# STM32_microcontroller_Power.net
KiCad netlist of a schematic drawn in Altium Designer
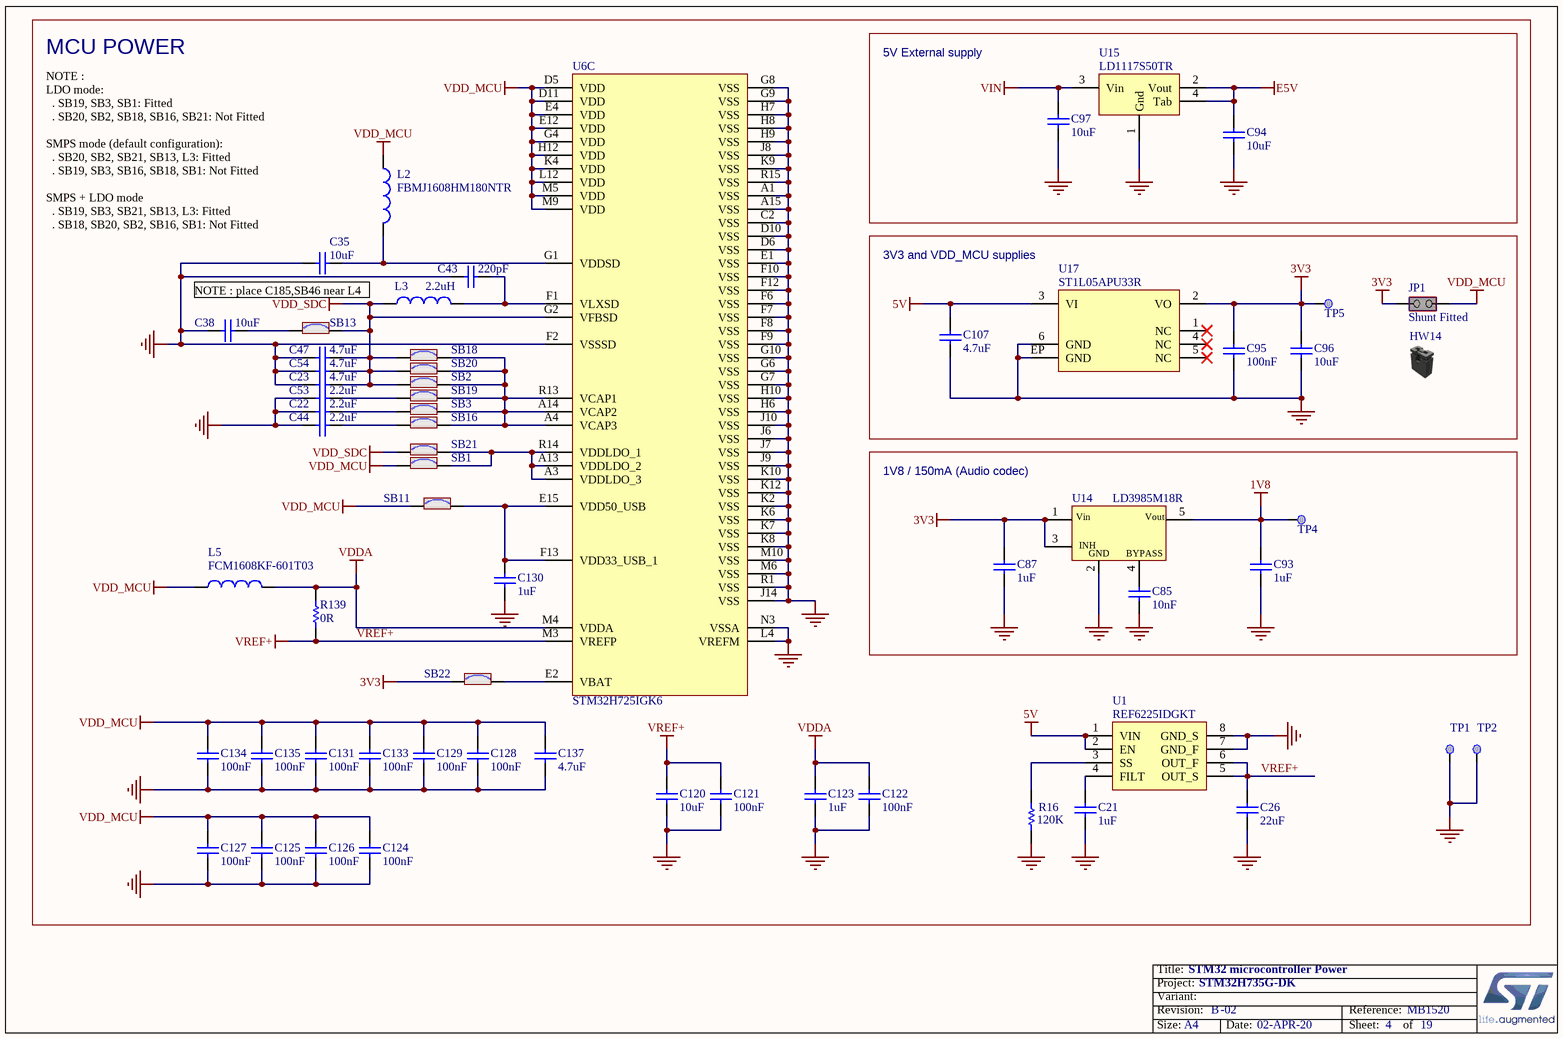
[diagram p0: STM32 microcontroller Power.SchDoc]

(export (version "E")
  (design (tool "Eeschema 10.0.6"))
  (components
    (comp (ref "C21")
      (value "1uF")
      (footprint "C0603")
      (description "Capacitor, MLCC, 1uF, 16V, X5R, 10%, 0603, T=0,8mm")
      (fields
        (field (name "INTERNAL_PART_NUMBER") "MCD-00010")
        (field (name "MANUFACTURER_PART_NUMBER") "CC0603KRX5R7BB105")
        (field (name "PROVIDED_BY") "SUBCO")
      )
      (libsource (lib "MCD_PARTS_database") (part "Capacitor"))
    )
    (comp (ref "C22")
      (value "2.2uF")
      (footprint "C0603")
      (description "Capacitor, MLCC, 2.2uF, 10V, X5R, 10%, 0603, T=0,8mm")
      (fields
        (field (name "INTERNAL_PART_NUMBER") "MCD-00012")
        (field (name "MANUFACTURER_PART_NUMBER") "CC0603KRX5R6BB225")
        (field (name "PROVIDED_BY") "SUBCO")
      )
      (libsource (lib "MCD_PARTS_database") (part "Capacitor"))
    )
    (comp (ref "C23")
      (value "4.7uF")
      (footprint "C0402")
      (description "Capacitor, MLCC, 4.7uF, 6V3, X5R, 20%, 0402, T=0,5mm")
      (fields
        (field (name "INTERNAL_PART_NUMBER") "MCD-01356")
        (field (name "MANUFACTURER_PART_NUMBER") "GRM155R60J475ME47")
        (field (name "PROVIDED_BY") "SUBCO")
      )
      (libsource (lib "MCD_PARTS_database") (part "Capacitor"))
    )
    (comp (ref "C26")
      (value "22uF")
      (footprint "C1210")
      (description "Capacitor, MLCC, 22uF, 16V, 1210, X7R, 20%, T=2,5mm, ESR 2mohm@410KHz")
      (fields
        (field (name "INTERNAL_PART_NUMBER") "MCD-00614")
        (field (name "MANUFACTURER_PART_NUMBER") "GCM32ER71C226ME19")
        (field (name "PROVIDED_BY") "SUBCO")
      )
      (libsource (lib "MCD_PARTS_database") (part "Capacitor"))
    )
    (comp (ref "C35")
      (value "10uF")
      (footprint "C0402")
      (description "Capacitor, MLCC, 10uF, 4V, X5R, 20%, 0402, T=0,5mm")
      (fields
        (field (name "INTERNAL_PART_NUMBER") "MCD-01355")
        (field (name "MANUFACTURER_PART_NUMBER") "GRM155R60G106ME44")
        (field (name "PROVIDED_BY") "SUBCO")
      )
      (libsource (lib "MCD_PARTS_database") (part "Capacitor"))
    )
    (comp (ref "C38")
      (value "10uF")
      (footprint "C0603")
      (description "Capacitor, MLCC, 10uF, 6V3, X5R, 20%, 0603, T=0,8mm")
      (fields
        (field (name "INTERNAL_PART_NUMBER") "MCD-01341")
        (field (name "MANUFACTURER_PART_NUMBER") "GRM188R60J106ME47D")
        (field (name "PROVIDED_BY") "SUBCO")
      )
      (libsource (lib "MCD_PARTS_database") (part "Capacitor"))
    )
    (comp (ref "C43")
      (value "220pF")
      (footprint "C0402")
      (description "Capacitor, MLCC, 220pF, 50V, NPO, 5%, 0402, T=0,5mm")
      (fields
        (field (name "INTERNAL_PART_NUMBER") "MCD-01225")
        (field (name "MANUFACTURER_PART_NUMBER") "CC0402JRNPO9BN221")
        (field (name "PROVIDED_BY") "SUBCO")
      )
      (libsource (lib "MCD_PARTS_database") (part "Capacitor"))
    )
    (comp (ref "C44")
      (value "2.2uF")
      (footprint "C0603")
      (description "Capacitor, MLCC, 2.2uF, 10V, X5R, 10%, 0603, T=0,8mm")
      (fields
        (field (name "INTERNAL_PART_NUMBER") "MCD-00012")
        (field (name "MANUFACTURER_PART_NUMBER") "CC0603KRX5R6BB225")
        (field (name "PROVIDED_BY") "SUBCO")
      )
      (libsource (lib "MCD_PARTS_database") (part "Capacitor"))
    )
    (comp (ref "C47")
      (value "4.7uF")
      (footprint "C0402")
      (description "Capacitor, MLCC, 4.7uF, 6V3, X5R, 20%, 0402, T=0,5mm")
      (fields
        (field (name "INTERNAL_PART_NUMBER") "MCD-01356")
        (field (name "MANUFACTURER_PART_NUMBER") "GRM155R60J475ME47")
        (field (name "PROVIDED_BY") "SUBCO")
      )
      (libsource (lib "MCD_PARTS_database") (part "Capacitor"))
    )
    (comp (ref "C53")
      (value "2.2uF")
      (footprint "C0603")
      (description "Capacitor, MLCC, 2.2uF, 10V, X5R, 10%, 0603, T=0,8mm")
      (fields
        (field (name "INTERNAL_PART_NUMBER") "MCD-00012")
        (field (name "MANUFACTURER_PART_NUMBER") "CC0603KRX5R6BB225")
        (field (name "PROVIDED_BY") "SUBCO")
      )
      (libsource (lib "MCD_PARTS_database") (part "Capacitor"))
    )
    (comp (ref "C54")
      (value "4.7uF")
      (footprint "C0402")
      (description "Capacitor, MLCC, 4.7uF, 6V3, X5R, 20%, 0402, T=0,5mm")
      (fields
        (field (name "INTERNAL_PART_NUMBER") "MCD-01356")
        (field (name "MANUFACTURER_PART_NUMBER") "GRM155R60J475ME47")
        (field (name "PROVIDED_BY") "SUBCO")
      )
      (libsource (lib "MCD_PARTS_database") (part "Capacitor"))
    )
    (comp (ref "C85")
      (value "10nF")
      (footprint "C0402")
      (description "Capacitor, MLCC, 10nF, 16V, X7R, 10%, 0402, T=0.5mm")
      (fields
        (field (name "INTERNAL_PART_NUMBER") "MCD-00011")
        (field (name "MANUFACTURER_PART_NUMBER") "CC0402KRX7R7BB103")
        (field (name "PROVIDED_BY") "SUBCO")
      )
      (libsource (lib "MCD_PARTS_database") (part "Capacitor"))
    )
    (comp (ref "C87")
      (value "1uF")
      (footprint "C0402")
      (description "Capacitor, MLCC, 1uF, 6V3, X5R, 10%, 0402, T=0,5mm")
      (fields
        (field (name "INTERNAL_PART_NUMBER") "MCD-00095")
        (field (name "MANUFACTURER_PART_NUMBER") "GRM155R61E105KA12")
        (field (name "PROVIDED_BY") "SUBCO")
      )
      (libsource (lib "MCD_PARTS_database") (part "Capacitor"))
    )
    (comp (ref "C93")
      (value "1uF")
      (footprint "C0402")
      (description "Capacitor, MLCC, 1uF, 6V3, X5R, 10%, 0402, T=0,5mm")
      (fields
        (field (name "INTERNAL_PART_NUMBER") "MCD-00095")
        (field (name "MANUFACTURER_PART_NUMBER") "GRM155R61E105KA12")
        (field (name "PROVIDED_BY") "SUBCO")
      )
      (libsource (lib "MCD_PARTS_database") (part "Capacitor"))
    )
    (comp (ref "C94")
      (value "10uF")
      (footprint "C0805")
      (description "Capacitor, MLCC, 10uF, 25V, X5R, 10%, 0805, T=0,85mm")
      (fields
        (field (name "INTERNAL_PART_NUMBER") "MCD-00014")
        (field (name "MANUFACTURER_PART_NUMBER") "CC0805KRX5R8BB106")
        (field (name "PROVIDED_BY") "SUBCO")
      )
      (libsource (lib "MCD_PARTS_database") (part "Capacitor"))
    )
    (comp (ref "C95")
      (value "100nF")
      (footprint "C0402")
      (description "Capacitor, MLCC, 100nF, 16V, X7R, 10%, 0402, T=0,5mm")
      (fields
        (field (name "INTERNAL_PART_NUMBER") "MCD-00102")
        (field (name "MANUFACTURER_PART_NUMBER") "CC0402KRX7R7BB104")
        (field (name "PROVIDED_BY") "SUBCO")
      )
      (libsource (lib "MCD_PARTS_database") (part "Capacitor"))
    )
    (comp (ref "C96")
      (value "10uF")
      (footprint "C0805")
      (description "Capacitor, MLCC, 10uF, 25V, X5R, 10%, 0805, T=0,85mm")
      (fields
        (field (name "INTERNAL_PART_NUMBER") "MCD-00014")
        (field (name "MANUFACTURER_PART_NUMBER") "CC0805KRX5R8BB106")
        (field (name "PROVIDED_BY") "SUBCO")
      )
      (libsource (lib "MCD_PARTS_database") (part "Capacitor"))
    )
    (comp (ref "C97")
      (value "10uF")
      (footprint "C0805")
      (description "Capacitor, MLCC, 10uF, 25V, X5R, 10%, 0805, T=0,85mm")
      (fields
        (field (name "INTERNAL_PART_NUMBER") "MCD-00014")
        (field (name "MANUFACTURER_PART_NUMBER") "CC0805KRX5R8BB106")
        (field (name "PROVIDED_BY") "SUBCO")
      )
      (libsource (lib "MCD_PARTS_database") (part "Capacitor"))
    )
    (comp (ref "C107")
      (value "4.7uF")
      (footprint "C0603")
      (description "Capacitor, MLCC, 4.7uF, 16V, X5R, 20%, 0603, T=0,8mm")
      (fields
        (field (name "INTERNAL_PART_NUMBER") "MCD-00097")
        (field (name "MANUFACTURER_PART_NUMBER") "GRM188R61C475KE11")
        (field (name "PROVIDED_BY") "SUBCO")
      )
      (libsource (lib "MCD_PARTS_database") (part "Capacitor"))
    )
    (comp (ref "C120")
      (value "10uF")
      (footprint "C0805")
      (description "Capacitor, MLCC, 10uF, 25V, X5R, 10%, 0805, T=0,85mm")
      (fields
        (field (name "INTERNAL_PART_NUMBER") "MCD-00014")
        (field (name "MANUFACTURER_PART_NUMBER") "CC0805KRX5R8BB106")
        (field (name "PROVIDED_BY") "SUBCO")
      )
      (libsource (lib "MCD_PARTS_database") (part "Capacitor"))
    )
    (comp (ref "C121")
      (value "100nF")
      (footprint "C0402")
      (description "Capacitor, MLCC, 100nF, 16V, X7R, 10%, 0402, T=0,5mm")
      (fields
        (field (name "INTERNAL_PART_NUMBER") "MCD-00102")
        (field (name "MANUFACTURER_PART_NUMBER") "CC0402KRX7R7BB104")
        (field (name "PROVIDED_BY") "SUBCO")
      )
      (libsource (lib "MCD_PARTS_database") (part "Capacitor"))
    )
    (comp (ref "C122")
      (value "100nF")
      (footprint "C0402")
      (description "Capacitor, MLCC, 100nF, 16V, X7R, 10%, 0402, T=0,5mm")
      (fields
        (field (name "INTERNAL_PART_NUMBER") "MCD-00102")
        (field (name "MANUFACTURER_PART_NUMBER") "CC0402KRX7R7BB104")
        (field (name "PROVIDED_BY") "SUBCO")
      )
      (libsource (lib "MCD_PARTS_database") (part "Capacitor"))
    )
    (comp (ref "C123")
      (value "1uF")
      (footprint "C0402")
      (description "Capacitor, 1uF, 10V, X5R, 10%, 0402, T=0.5mm")
      (fields
        (field (name "INTERNAL_PART_NUMBER") "MCD-01722")
        (field (name "MANUFACTURER_PART_NUMBER") "CC0402KRX5R6BB105")
        (field (name "PROVIDED_BY") "SUBCO")
      )
      (libsource (lib "MCD_PARTS_database") (part "Capacitor"))
    )
    (comp (ref "C124")
      (value "100nF")
      (footprint "C0402")
      (description "Capacitor, MLCC, 100nF, 16V, X7R, 10%, 0402, T=0,5mm")
      (fields
        (field (name "INTERNAL_PART_NUMBER") "MCD-00102")
        (field (name "MANUFACTURER_PART_NUMBER") "CC0402KRX7R7BB104")
        (field (name "PROVIDED_BY") "SUBCO")
      )
      (libsource (lib "MCD_PARTS_database") (part "Capacitor"))
    )
    (comp (ref "C125")
      (value "100nF")
      (footprint "C0402")
      (description "Capacitor, MLCC, 100nF, 16V, X7R, 10%, 0402, T=0,5mm")
      (fields
        (field (name "INTERNAL_PART_NUMBER") "MCD-00102")
        (field (name "MANUFACTURER_PART_NUMBER") "CC0402KRX7R7BB104")
        (field (name "PROVIDED_BY") "SUBCO")
      )
      (libsource (lib "MCD_PARTS_database") (part "Capacitor"))
    )
    (comp (ref "C126")
      (value "100nF")
      (footprint "C0402")
      (description "Capacitor, MLCC, 100nF, 16V, X7R, 10%, 0402, T=0,5mm")
      (fields
        (field (name "INTERNAL_PART_NUMBER") "MCD-00102")
        (field (name "MANUFACTURER_PART_NUMBER") "CC0402KRX7R7BB104")
        (field (name "PROVIDED_BY") "SUBCO")
      )
      (libsource (lib "MCD_PARTS_database") (part "Capacitor"))
    )
    (comp (ref "C127")
      (value "100nF")
      (footprint "C0402")
      (description "Capacitor, MLCC, 100nF, 16V, X7R, 10%, 0402, T=0,5mm")
      (fields
        (field (name "INTERNAL_PART_NUMBER") "MCD-00102")
        (field (name "MANUFACTURER_PART_NUMBER") "CC0402KRX7R7BB104")
        (field (name "PROVIDED_BY") "SUBCO")
      )
      (libsource (lib "MCD_PARTS_database") (part "Capacitor"))
    )
    (comp (ref "C128")
      (value "100nF")
      (footprint "C0402")
      (description "Capacitor, MLCC, 100nF, 16V, X7R, 10%, 0402, T=0,5mm")
      (fields
        (field (name "INTERNAL_PART_NUMBER") "MCD-00102")
        (field (name "MANUFACTURER_PART_NUMBER") "CC0402KRX7R7BB104")
        (field (name "PROVIDED_BY") "SUBCO")
      )
      (libsource (lib "MCD_PARTS_database") (part "Capacitor"))
    )
    (comp (ref "C129")
      (value "100nF")
      (footprint "C0402")
      (description "Capacitor, MLCC, 100nF, 16V, X7R, 10%, 0402, T=0,5mm")
      (fields
        (field (name "INTERNAL_PART_NUMBER") "MCD-00102")
        (field (name "MANUFACTURER_PART_NUMBER") "CC0402KRX7R7BB104")
        (field (name "PROVIDED_BY") "SUBCO")
      )
      (libsource (lib "MCD_PARTS_database") (part "Capacitor"))
    )
    (comp (ref "C130")
      (value "1uF")
      (footprint "C0603")
      (description "Capacitor, MLCC, 1uF, 16V, X5R, 10%, 0603, T=0,8mm")
      (fields
        (field (name "INTERNAL_PART_NUMBER") "MCD-00010")
        (field (name "MANUFACTURER_PART_NUMBER") "CC0603KRX5R7BB105")
        (field (name "PROVIDED_BY") "SUBCO")
      )
      (libsource (lib "MCD_PARTS_database") (part "Capacitor"))
    )
    (comp (ref "C131")
      (value "100nF")
      (footprint "C0402")
      (description "Capacitor, MLCC, 100nF, 16V, X7R, 10%, 0402, T=0,5mm")
      (fields
        (field (name "INTERNAL_PART_NUMBER") "MCD-00102")
        (field (name "MANUFACTURER_PART_NUMBER") "CC0402KRX7R7BB104")
        (field (name "PROVIDED_BY") "SUBCO")
      )
      (libsource (lib "MCD_PARTS_database") (part "Capacitor"))
    )
    (comp (ref "C133")
      (value "100nF")
      (footprint "C0402")
      (description "Capacitor, MLCC, 100nF, 16V, X7R, 10%, 0402, T=0,5mm")
      (fields
        (field (name "INTERNAL_PART_NUMBER") "MCD-00102")
        (field (name "MANUFACTURER_PART_NUMBER") "CC0402KRX7R7BB104")
        (field (name "PROVIDED_BY") "SUBCO")
      )
      (libsource (lib "MCD_PARTS_database") (part "Capacitor"))
    )
    (comp (ref "C134")
      (value "100nF")
      (footprint "C0402")
      (description "Capacitor, MLCC, 100nF, 16V, X7R, 10%, 0402, T=0,5mm")
      (fields
        (field (name "INTERNAL_PART_NUMBER") "MCD-00102")
        (field (name "MANUFACTURER_PART_NUMBER") "CC0402KRX7R7BB104")
        (field (name "PROVIDED_BY") "SUBCO")
      )
      (libsource (lib "MCD_PARTS_database") (part "Capacitor"))
    )
    (comp (ref "C135")
      (value "100nF")
      (footprint "C0402")
      (description "Capacitor, MLCC, 100nF, 16V, X7R, 10%, 0402, T=0,5mm")
      (fields
        (field (name "INTERNAL_PART_NUMBER") "MCD-00102")
        (field (name "MANUFACTURER_PART_NUMBER") "CC0402KRX7R7BB104")
        (field (name "PROVIDED_BY") "SUBCO")
      )
      (libsource (lib "MCD_PARTS_database") (part "Capacitor"))
    )
    (comp (ref "C137")
      (value "4.7uF")
      (footprint "C0402")
      (description "Capacitor, MLCC, 4.7uF, 6V3, X5R, 20%, 0402, T=0,5mm")
      (fields
        (field (name "INTERNAL_PART_NUMBER") "MCD-01356")
        (field (name "MANUFACTURER_PART_NUMBER") "GRM155R60J475ME47")
        (field (name "PROVIDED_BY") "SUBCO")
      )
      (libsource (lib "MCD_PARTS_database") (part "Capacitor"))
    )
    (comp (ref "HW14")
      (value "Shunt Black 2.54mm")
      (description "SHUNT 2.54mm BLACK")
      (fields
        (field (name "INTERNAL_PART_NUMBER") "MCD-00043")
        (field (name "MANUFACTURER_PART_NUMBER") "SNT-100-BK-G")
        (field (name "PROVIDED_BY") "SUBCO")
      )
      (libsource (lib "MCD_PARTS_database") (part "Shunt Black 2.54mm"))
    )
    (comp (ref "JP1")
      (value "Shunt Fitted")
      (footprint "CON_SAMTEC_TSW-102-07-G-S")
      (description "Header, 2x1, 2,54mm, VR, TH, Height 5.84mm/2.54mm - Shunt Fitted by default")
      (fields
        (field (name "INTERNAL_PART_NUMBER") "MCD-00683")
        (field (name "MANUFACTURER_PART_NUMBER") "TSW-102-07-x-S")
        (field (name "PROVIDED_BY") "SUBCO")
      )
      (libsource (lib "MCD_PARTS_database") (part "Jumper_Header 2x1 Fitted"))
    )
    (comp (ref "L2")
      (value "FBMJ1608HM180NTR")
      (footprint "IND_TAIYO-YUDEN_FBMJ1608")
      (description "Ferrite Bead 18 ohm@100MHz 0603")
      (fields
        (field (name "INTERNAL_PART_NUMBER") "MCD-01431")
        (field (name "MANUFACTURER") "TAIYO YUDEN")
        (field (name "PROVIDED_BY") "SUBCO")
      )
      (libsource (lib "MCD_PARTS_database") (part "Inductor"))
    )
    (comp (ref "L3")
      (value "2.2uH")
      (footprint "IND_2016_MURATA_LQM2MPN2R2NG0")
      (description "Inductor 2.2uH, 2x1.6x0.9mm")
      (fields
        (field (name "INTERNAL_PART_NUMBER") "MCD-01110")
        (field (name "MANUFACTURER_PART_NUMBER") "LQM2MPN2R2NG0")
        (field (name "PROVIDED_BY") "SUBCO")
      )
      (libsource (lib "MCD_PARTS_database") (part "Inductor"))
    )
    (comp (ref "L5")
      (value "BEAD")
      (footprint "L0603")
      (description "SMD Chip ferrite bead, 600R@100MHz +/-25%, 350mA, 500mohm DC, 0603, T=0.8mm")
      (fields
        (field (name "INTERNAL_PART_NUMBER") "MCD-00047")
        (field (name "MANUFACTURER_PART_NUMBER") "FCM1608KF-601T03")
        (field (name "MANUFACTURER") "TAI-TECH")
        (field (name "PROVIDED_BY") "SUBCO")
      )
      (libsource (lib "MCD_PARTS_database") (part "BEAD"))
    )
    (comp (ref "R16")
      (value "120K")
      (footprint "R0402")
      (description "Resistor,120K,0402,1%,1/16W")
      (fields
        (field (name "INTERNAL_PART_NUMBER") "MCD-00166")
        (field (name "MANUFACTURER_PART_NUMBER") "RC0402FR-07120KL")
        (field (name "PROVIDED_BY") "SUBCO")
      )
      (libsource (lib "MCD_PARTS_database") (part "Resistor"))
    )
    (comp (ref "R139")
      (value "0R")
      (footprint "R0603")
      (description "Resistor,0R,0603,5%,1/10W")
      (fields
        (field (name "INTERNAL_PART_NUMBER") "MCD-00056")
        (field (name "MANUFACTURER_PART_NUMBER") "RC0603JR-070RL")
        (field (name "PROVIDED_BY") "SUBCO")
      )
      (libsource (lib "MCD_PARTS_database") (part "Resistor"))
    )
    (comp (ref "SB1")
      (value "SB_ON")
      (footprint "SOLDER-BRIDGE_R0603-0R")
      (description "Solder Bridge ON")
      (fields
        (field (name "INTERNAL_PART_NUMBER") "MCD-00071")
        (field (name "MANUFACTURER_PART_NUMBER") "RC0603JR-070RL")
        (field (name "PROVIDED_BY") "SUBCO")
      )
      (libsource (lib "MCD_PARTS_database") (part "SB_ON"))
    )
    (comp (ref "SB2")
      (value "SB_ON")
      (footprint "SOLDER-BRIDGE_R0603-0R")
      (description "Solder Bridge ON")
      (fields
        (field (name "INTERNAL_PART_NUMBER") "MCD-00071")
        (field (name "MANUFACTURER_PART_NUMBER") "RC0603JR-070RL")
        (field (name "PROVIDED_BY") "SUBCO")
      )
      (libsource (lib "MCD_PARTS_database") (part "SB_ON"))
    )
    (comp (ref "SB3")
      (value "SB_ON")
      (footprint "SOLDER-BRIDGE_R0603-0R")
      (description "Solder Bridge ON")
      (fields
        (field (name "INTERNAL_PART_NUMBER") "MCD-00071")
        (field (name "MANUFACTURER_PART_NUMBER") "RC0603JR-070RL")
        (field (name "PROVIDED_BY") "SUBCO")
      )
      (libsource (lib "MCD_PARTS_database") (part "SB_ON"))
    )
    (comp (ref "SB11")
      (value "SB_ON")
      (footprint "SOLDER-BRIDGE_R0603-0R")
      (description "Solder Bridge ON")
      (fields
        (field (name "INTERNAL_PART_NUMBER") "MCD-00071")
        (field (name "MANUFACTURER_PART_NUMBER") "RC0603JR-070RL")
        (field (name "PROVIDED_BY") "SUBCO")
      )
      (libsource (lib "MCD_PARTS_database") (part "SB_ON"))
    )
    (comp (ref "SB13")
      (value "SB_ON")
      (footprint "SOLDER-BRIDGE_R0603-0R")
      (description "Solder Bridge ON")
      (fields
        (field (name "INTERNAL_PART_NUMBER") "MCD-00071")
        (field (name "MANUFACTURER_PART_NUMBER") "RC0603JR-070RL")
        (field (name "PROVIDED_BY") "SUBCO")
      )
      (libsource (lib "MCD_PARTS_database") (part "SB_ON"))
    )
    (comp (ref "SB16")
      (value "SB_ON")
      (footprint "SOLDER-BRIDGE_R0603-0R")
      (description "Solder Bridge ON")
      (fields
        (field (name "INTERNAL_PART_NUMBER") "MCD-00071")
        (field (name "MANUFACTURER_PART_NUMBER") "RC0603JR-070RL")
        (field (name "PROVIDED_BY") "SUBCO")
      )
      (libsource (lib "MCD_PARTS_database") (part "SB_ON"))
    )
    (comp (ref "SB18")
      (value "SB_ON")
      (footprint "SOLDER-BRIDGE_R0603-0R")
      (description "Solder Bridge ON")
      (fields
        (field (name "INTERNAL_PART_NUMBER") "MCD-00071")
        (field (name "MANUFACTURER_PART_NUMBER") "RC0603JR-070RL")
        (field (name "PROVIDED_BY") "SUBCO")
      )
      (libsource (lib "MCD_PARTS_database") (part "SB_ON"))
    )
    (comp (ref "SB19")
      (value "SB_ON")
      (footprint "SOLDER-BRIDGE_R0603-0R")
      (description "Solder Bridge ON")
      (fields
        (field (name "INTERNAL_PART_NUMBER") "MCD-00071")
        (field (name "MANUFACTURER_PART_NUMBER") "RC0603JR-070RL")
        (field (name "PROVIDED_BY") "SUBCO")
      )
      (libsource (lib "MCD_PARTS_database") (part "SB_ON"))
    )
    (comp (ref "SB20")
      (value "SB_ON")
      (footprint "SOLDER-BRIDGE_R0603-0R")
      (description "Solder Bridge ON")
      (fields
        (field (name "INTERNAL_PART_NUMBER") "MCD-00071")
        (field (name "MANUFACTURER_PART_NUMBER") "RC0603JR-070RL")
        (field (name "PROVIDED_BY") "SUBCO")
      )
      (libsource (lib "MCD_PARTS_database") (part "SB_ON"))
    )
    (comp (ref "SB21")
      (value "SB_ON")
      (footprint "SOLDER-BRIDGE_R0603-0R")
      (description "Solder Bridge ON")
      (fields
        (field (name "INTERNAL_PART_NUMBER") "MCD-00071")
        (field (name "MANUFACTURER_PART_NUMBER") "RC0603JR-070RL")
        (field (name "PROVIDED_BY") "SUBCO")
      )
      (libsource (lib "MCD_PARTS_database") (part "SB_ON"))
    )
    (comp (ref "SB22")
      (value "SB_ON")
      (footprint "SOLDER-BRIDGE_R0603-0R")
      (description "Solder Bridge ON")
      (fields
        (field (name "INTERNAL_PART_NUMBER") "MCD-00071")
        (field (name "MANUFACTURER_PART_NUMBER") "RC0603JR-070RL")
        (field (name "PROVIDED_BY") "SUBCO")
      )
      (libsource (lib "MCD_PARTS_database") (part "SB_ON"))
    )
    (comp (ref "TP1")
      (value "Test Point")
      (footprint "TP_SMD_0-3MM")
      (description "Test Point 0.3mm")
      (fields (field (name "INTERNAL_PART_NUMBER") "MCD-00630"))
      (libsource (lib "MCD_PARTS_database") (part "Test Point"))
    )
    (comp (ref "TP2")
      (value "Test Point")
      (footprint "TP_SMD_0-3MM")
      (description "Test Point 0.3mm")
      (fields (field (name "INTERNAL_PART_NUMBER") "MCD-00630"))
      (libsource (lib "MCD_PARTS_database") (part "Test Point"))
    )
    (comp (ref "TP4")
      (value "Test Point")
      (footprint "TP_SMD_0-3MM")
      (description "Test Point 0.3mm")
      (fields (field (name "INTERNAL_PART_NUMBER") "MCD-00630"))
      (libsource (lib "") (part "Test Point_1"))
    )
    (comp (ref "TP5")
      (value "Test Point")
      (footprint "TP_SMD_0-3MM")
      (description "Test Point 0.3mm")
      (fields (field (name "INTERNAL_PART_NUMBER") "MCD-00630"))
      (libsource (lib "") (part "Test Point_1"))
    )
    (comp (ref "U1")
      (value "REF6225IDGKT")
      (footprint "ICC_VSSOP8_DGK_S-PDSO-G8_3X3_P065")
      (description "IC VREF SERIES 2.5V 8VSSOP")
      (fields
        (field (name "INTERNAL_PART_NUMBER") "MCD-01138")
        (field (name "MANUFACTURER") "TI")
        (field (name "PROVIDED_BY") "SUBCO")
      )
      (libsource (lib "MCD_PARTS_database") (part "REF6225IDGKT"))
    )
    (comp (ref "U6")
      (value "STM32H725IGK6")
      (footprint "ICC_UFBGA201_176+25_10X10_P065")
      (description "STM32H725IGK6 MCU, Cut1.0, 10x10x0.6mm, Pitch0.65mm, Int SMPS")
      (fields
        (field (name "INTERNAL_PART_NUMBER") "MCD-01673")
        (field (name "MANUFACTURER") "STMICROELECTRONICS")
        (field (name "PROVIDED_BY") "SUBCO with ST control")
      )
      (libsource (lib "MCD_PARTS_database") (part "STM32H725IGK6U"))
    )
    (comp (ref "U14")
      (value "LD3985M18R")
      (footprint "REG_SOT23-5L")
      (description "Ultra low drop-low noise BiCMOS voltage, regulators low ESR capacitors compatible")
      (fields
        (field (name "INTERNAL_PART_NUMBER") "MCD-00078")
        (field (name "MANUFACTURER") "STMICROELECTRONICS")
        (field (name "PROVIDED_BY") "SUBCO with ST control")
      )
      (libsource (lib "MCD_PARTS_database") (part "LD3985M18R"))
    )
    (comp (ref "U15")
      (value "LD1117S50TR")
      (footprint "REG_SOT223-TAB")
      (description "IC REG LDO 5V 0.8A SOT223")
      (fields
        (field (name "INTERNAL_PART_NUMBER") "MCD-00088")
        (field (name "MANUFACTURER") "STMICROELECTRONICS")
        (field (name "PROVIDED_BY") "SUBCO with ST control")
      )
      (libsource (lib "MCD_PARTS_database") (part "LD1117S50TR"))
    )
    (comp (ref "U17")
      (value "ST1L05APU33R")
      (footprint "ICC_DFN6-EPAD_3X3_P095")
      (description "IC REG LDO 3.3V 1.3A 6DFN")
      (fields
        (field (name "INTERNAL_PART_NUMBER") "MCD-01127")
        (field (name "MANUFACTURER") "STMICROELECTRONICS")
        (field (name "PROVIDED_BY") "SUBCO with ST control")
      )
      (libsource (lib "MCD_PARTS_database") (part "ST1L05APU33R"))
    )
  )
  (nets
    (net (code "1") (name "1V8") (class "Default")
      (node (ref "C93") (pin "2") (pinfunction "2_2") (pintype "passive"))
      (node (ref "TP4") (pin "1") (pinfunction "1_1") (pintype "passive"))
      (node (ref "U14") (pin "5") (pinfunction "Vout_5") (pintype "passive"))
    )
    (net (code "2") (name "3V3") (class "Default")
      (node (ref "C87") (pin "2") (pinfunction "2_2") (pintype "passive"))
      (node (ref "C95") (pin "1") (pinfunction "1_1") (pintype "passive"))
      (node (ref "C96") (pin "2") (pinfunction "2_2") (pintype "passive"))
      (node (ref "JP1") (pin "2") (pinfunction "NO_2") (pintype "passive"))
      (node (ref "SB22") (pin "1") (pinfunction "1_1") (pintype "passive"))
      (node (ref "TP5") (pin "1") (pinfunction "1_1") (pintype "passive"))
      (node (ref "U14") (pin "1") (pinfunction "Vin_1") (pintype "passive"))
      (node (ref "U14") (pin "3") (pinfunction "CE_3") (pintype "passive"))
      (node (ref "U17") (pin "2") (pinfunction "VO_2") (pintype "passive"))
    )
    (net (code "3") (name "5V") (class "Default")
      (node (ref "C107") (pin "2") (pinfunction "2_2") (pintype "passive"))
      (node (ref "U1") (pin "1") (pinfunction "VIN_1") (pintype "passive"))
      (node (ref "U1") (pin "2") (pinfunction "EN_2") (pintype "passive"))
      (node (ref "U17") (pin "3") (pinfunction "VI_3") (pintype "passive"))
    )
    (net (code "4") (name "E5V") (class "Default")
      (node (ref "C94") (pin "2") (pinfunction "2_2") (pintype "passive"))
      (node (ref "U15") (pin "2") (pinfunction "Vout_2") (pintype "passive"))
      (node (ref "U15") (pin "4") (pinfunction "Tab_4") (pintype "passive"))
    )
    (net (code "5") (name "GND") (class "Default")
      (node (ref "C107") (pin "1") (pinfunction "1_1") (pintype "passive"))
      (node (ref "C120") (pin "1") (pinfunction "1_1") (pintype "passive"))
      (node (ref "C121") (pin "1") (pinfunction "1_1") (pintype "passive"))
      (node (ref "C122") (pin "1") (pinfunction "1_1") (pintype "passive"))
      (node (ref "C123") (pin "2") (pinfunction "2_2") (pintype "passive"))
      (node (ref "C124") (pin "1") (pinfunction "1_1") (pintype "passive"))
      (node (ref "C125") (pin "1") (pinfunction "1_1") (pintype "passive"))
      (node (ref "C126") (pin "1") (pinfunction "1_1") (pintype "passive"))
      (node (ref "C127") (pin "1") (pinfunction "1_1") (pintype "passive"))
      (node (ref "C128") (pin "1") (pinfunction "1_1") (pintype "passive"))
      (node (ref "C129") (pin "1") (pinfunction "1_1") (pintype "passive"))
      (node (ref "C130") (pin "2") (pinfunction "2_2") (pintype "passive"))
      (node (ref "C131") (pin "1") (pinfunction "1_1") (pintype "passive"))
      (node (ref "C133") (pin "1") (pinfunction "1_1") (pintype "passive"))
      (node (ref "C134") (pin "1") (pinfunction "1_1") (pintype "passive"))
      (node (ref "C135") (pin "1") (pinfunction "1_1") (pintype "passive"))
      (node (ref "C137") (pin "1") (pinfunction "1_1") (pintype "passive"))
      (node (ref "C21") (pin "1") (pinfunction "1_1") (pintype "passive"))
      (node (ref "C22") (pin "1") (pinfunction "1_1") (pintype "passive"))
      (node (ref "C23") (pin "2") (pinfunction "2_2") (pintype "passive"))
      (node (ref "C26") (pin "1") (pinfunction "1_1") (pintype "passive"))
      (node (ref "C35") (pin "1") (pinfunction "1_1") (pintype "passive"))
      (node (ref "C38") (pin "1") (pinfunction "1_1") (pintype "passive"))
      (node (ref "C43") (pin "1") (pinfunction "1_1") (pintype "passive"))
      (node (ref "C44") (pin "1") (pinfunction "1_1") (pintype "passive"))
      (node (ref "C47") (pin "2") (pinfunction "2_2") (pintype "passive"))
      (node (ref "C53") (pin "1") (pinfunction "1_1") (pintype "passive"))
      (node (ref "C54") (pin "2") (pinfunction "2_2") (pintype "passive"))
      (node (ref "C85") (pin "1") (pinfunction "1_1") (pintype "passive"))
      (node (ref "C87") (pin "1") (pinfunction "1_1") (pintype "passive"))
      (node (ref "C93") (pin "1") (pinfunction "1_1") (pintype "passive"))
      (node (ref "C94") (pin "1") (pinfunction "1_1") (pintype "passive"))
      (node (ref "C95") (pin "2") (pinfunction "2_2") (pintype "passive"))
      (node (ref "C96") (pin "1") (pinfunction "1_1") (pintype "passive"))
      (node (ref "C97") (pin "1") (pinfunction "1_1") (pintype "passive"))
      (node (ref "R16") (pin "1") (pinfunction "1_1") (pintype "passive"))
      (node (ref "TP1") (pin "1") (pinfunction "1_1") (pintype "passive"))
      (node (ref "TP2") (pin "1") (pinfunction "1_1") (pintype "passive"))
      (node (ref "U1") (pin "7") (pinfunction "GND_F_7") (pintype "passive"))
      (node (ref "U1") (pin "8") (pinfunction "GND_S_8") (pintype "passive"))
      (node (ref "U14") (pin "2") (pinfunction "GND_2") (pintype "passive"))
      (node (ref "U15") (pin "1") (pinfunction "Gnd_1") (pintype "passive"))
      (node (ref "U17") (pin "6") (pinfunction "GND_6") (pintype "passive"))
      (node (ref "U17") (pin "EP") (pinfunction "GND_EP") (pintype "passive"))
      (node (ref "U6") (pin "A1") (pinfunction "VSS_A1") (pintype "passive"))
      (node (ref "U6") (pin "A15") (pinfunction "VSS_A15") (pintype "passive"))
      (node (ref "U6") (pin "C2") (pinfunction "VSS_C2") (pintype "passive"))
      (node (ref "U6") (pin "D10") (pinfunction "VSS_D10") (pintype "passive"))
      (node (ref "U6") (pin "D6") (pinfunction "VSS_D6") (pintype "passive"))
      (node (ref "U6") (pin "E1") (pinfunction "VSS_E1") (pintype "passive"))
      (node (ref "U6") (pin "F10") (pinfunction "VSS_F10") (pintype "passive"))
      (node (ref "U6") (pin "F12") (pinfunction "VSS_F12") (pintype "passive"))
      (node (ref "U6") (pin "F2") (pinfunction "VSSSD_F2") (pintype "passive"))
      (node (ref "U6") (pin "F6") (pinfunction "VSS_F6") (pintype "passive"))
      (node (ref "U6") (pin "F7") (pinfunction "VSS_F7") (pintype "passive"))
      (node (ref "U6") (pin "F8") (pinfunction "VSS_F8") (pintype "passive"))
      (node (ref "U6") (pin "F9") (pinfunction "VSS_F9") (pintype "passive"))
      (node (ref "U6") (pin "G10") (pinfunction "VSS_G10") (pintype "passive"))
      (node (ref "U6") (pin "G6") (pinfunction "VSS_G6") (pintype "passive"))
      (node (ref "U6") (pin "G7") (pinfunction "VSS_G7") (pintype "passive"))
      (node (ref "U6") (pin "G8") (pinfunction "VSS_G8") (pintype "passive"))
      (node (ref "U6") (pin "G9") (pinfunction "VSS_G9") (pintype "passive"))
      (node (ref "U6") (pin "H10") (pinfunction "VSS_H10") (pintype "passive"))
      (node (ref "U6") (pin "H6") (pinfunction "VSS_H6") (pintype "passive"))
      (node (ref "U6") (pin "H7") (pinfunction "VSS_H7") (pintype "passive"))
      (node (ref "U6") (pin "H8") (pinfunction "VSS_H8") (pintype "passive"))
      (node (ref "U6") (pin "H9") (pinfunction "VSS_H9") (pintype "passive"))
      (node (ref "U6") (pin "J10") (pinfunction "VSS_J10") (pintype "passive"))
      (node (ref "U6") (pin "J14") (pinfunction "VSS_J14") (pintype "passive"))
      (node (ref "U6") (pin "J6") (pinfunction "VSS_J6") (pintype "passive"))
      (node (ref "U6") (pin "J7") (pinfunction "VSS_J7") (pintype "passive"))
      (node (ref "U6") (pin "J8") (pinfunction "VSS_J8") (pintype "passive"))
      (node (ref "U6") (pin "J9") (pinfunction "VSS_J9") (pintype "passive"))
      (node (ref "U6") (pin "K10") (pinfunction "VSS_K10") (pintype "passive"))
      (node (ref "U6") (pin "K12") (pinfunction "VSS_K12") (pintype "passive"))
      (node (ref "U6") (pin "K2") (pinfunction "VSS_K2") (pintype "passive"))
      (node (ref "U6") (pin "K6") (pinfunction "VSS_K6") (pintype "passive"))
      (node (ref "U6") (pin "K7") (pinfunction "VSS_K7") (pintype "passive"))
      (node (ref "U6") (pin "K8") (pinfunction "VSS_K8") (pintype "passive"))
      (node (ref "U6") (pin "K9") (pinfunction "VSS_K9") (pintype "passive"))
      (node (ref "U6") (pin "L4") (pinfunction "VREFM_L4") (pintype "passive"))
      (node (ref "U6") (pin "M10") (pinfunction "VSS_M10") (pintype "passive"))
      (node (ref "U6") (pin "M6") (pinfunction "VSS_M6") (pintype "passive"))
      (node (ref "U6") (pin "N3") (pinfunction "VSSA_N3") (pintype "passive"))
      (node (ref "U6") (pin "R1") (pinfunction "VSS_R1") (pintype "passive"))
      (node (ref "U6") (pin "R15") (pinfunction "VSS_R15") (pintype "passive"))
    )
    (net (code "6") (name "Net-(C22-Pad2)") (class "Default")
      (node (ref "C22") (pin "2") (pinfunction "2_2") (pintype "passive"))
      (node (ref "SB3") (pin "1") (pinfunction "1_1") (pintype "passive"))
    )
    (net (code "7") (name "Net-(C38-Pad2)") (class "Default")
      (node (ref "C38") (pin "2") (pinfunction "2_2") (pintype "passive"))
      (node (ref "SB13") (pin "1") (pinfunction "1_1") (pintype "passive"))
    )
    (net (code "8") (name "Net-(C44-Pad2)") (class "Default")
      (node (ref "C44") (pin "2") (pinfunction "2_2") (pintype "passive"))
      (node (ref "SB16") (pin "1") (pinfunction "1_1") (pintype "passive"))
    )
    (net (code "9") (name "Net-(C53-Pad2)") (class "Default")
      (node (ref "C53") (pin "2") (pinfunction "2_2") (pintype "passive"))
      (node (ref "SB19") (pin "1") (pinfunction "1_1") (pintype "passive"))
    )
    (net (code "10") (name "Net-(U1-FILT)") (class "Default")
      (node (ref "C21") (pin "2") (pinfunction "2_2") (pintype "passive"))
      (node (ref "U1") (pin "4") (pinfunction "FILT_4") (pintype "passive"))
    )
    (net (code "11") (name "Net-(U1-SS)") (class "Default")
      (node (ref "R16") (pin "2") (pinfunction "2_2") (pintype "passive"))
      (node (ref "U1") (pin "3") (pinfunction "SS_3") (pintype "passive"))
    )
    (net (code "12") (name "Net-(U6C-VBAT)") (class "Default")
      (node (ref "SB22") (pin "2") (pinfunction "2_2") (pintype "passive"))
      (node (ref "U6") (pin "E2") (pinfunction "VBAT_E2") (pintype "passive"))
    )
    (net (code "13") (name "Net-(U6C-VCAP1)") (class "Default")
      (node (ref "SB16") (pin "2") (pinfunction "2_2") (pintype "passive"))
      (node (ref "SB18") (pin "2") (pinfunction "2_2") (pintype "passive"))
      (node (ref "SB19") (pin "2") (pinfunction "2_2") (pintype "passive"))
      (node (ref "SB2") (pin "2") (pinfunction "2_2") (pintype "passive"))
      (node (ref "SB20") (pin "2") (pinfunction "2_2") (pintype "passive"))
      (node (ref "SB3") (pin "2") (pinfunction "2_2") (pintype "passive"))
      (node (ref "U6") (pin "A14") (pinfunction "VCAP2_A14") (pintype "passive"))
      (node (ref "U6") (pin "A4") (pinfunction "VCAP3_A4") (pintype "passive"))
      (node (ref "U6") (pin "R13") (pinfunction "VCAP1_R13") (pintype "passive"))
    )
    (net (code "14") (name "Net-(U6C-VDD33_USB_1)") (class "Default")
      (node (ref "C130") (pin "1") (pinfunction "1_1") (pintype "passive"))
      (node (ref "SB11") (pin "2") (pinfunction "2_2") (pintype "passive"))
      (node (ref "U6") (pin "E15") (pinfunction "VDD50_USB_E15") (pintype "passive"))
      (node (ref "U6") (pin "F13") (pinfunction "VDD33_USB_1_F13") (pintype "passive"))
    )
    (net (code "15") (name "Net-(U6C-VDDLDO_1)") (class "Default")
      (node (ref "SB1") (pin "2") (pinfunction "2_2") (pintype "passive"))
      (node (ref "SB21") (pin "2") (pinfunction "2_2") (pintype "passive"))
      (node (ref "U6") (pin "A13") (pinfunction "VDDLDO_2_A13") (pintype "passive"))
      (node (ref "U6") (pin "A3") (pinfunction "VDDLDO_3_A3") (pintype "passive"))
      (node (ref "U6") (pin "R14") (pinfunction "VDDLDO_1_R14") (pintype "passive"))
    )
    (net (code "16") (name "Net-(U6C-VDDSD)") (class "Default")
      (node (ref "C35") (pin "2") (pinfunction "2_2") (pintype "passive"))
      (node (ref "L2") (pin "2") (pinfunction "2_2") (pintype "passive"))
      (node (ref "U6") (pin "G1") (pinfunction "VDDSD_G1") (pintype "passive"))
    )
    (net (code "17") (name "Net-(U6C-VLXSD)") (class "Default")
      (node (ref "C43") (pin "2") (pinfunction "2_2") (pintype "passive"))
      (node (ref "L3") (pin "2") (pinfunction "2_2") (pintype "passive"))
      (node (ref "U6") (pin "F1") (pinfunction "VLXSD_F1") (pintype "passive"))
    )
    (net (code "18") (name "Net-(U14-BYPASS)") (class "Default")
      (node (ref "C85") (pin "2") (pinfunction "2_2") (pintype "passive"))
      (node (ref "U14") (pin "4") (pinfunction "BYPASS_4") (pintype "passive"))
    )
    (net (code "19") (name "VDDA") (class "Default")
      (node (ref "C122") (pin "2") (pinfunction "2_2") (pintype "passive"))
      (node (ref "C123") (pin "1") (pinfunction "1_1") (pintype "passive"))
      (node (ref "L5") (pin "2") (pinfunction "2_2") (pintype "passive"))
      (node (ref "R139") (pin "2") (pinfunction "2_2") (pintype "passive"))
      (node (ref "U6") (pin "M4") (pinfunction "VDDA_M4") (pintype "passive"))
    )
    (net (code "20") (name "VDD_MCU") (class "Default")
      (node (ref "C124") (pin "2") (pinfunction "2_2") (pintype "passive"))
      (node (ref "C125") (pin "2") (pinfunction "2_2") (pintype "passive"))
      (node (ref "C126") (pin "2") (pinfunction "2_2") (pintype "passive"))
      (node (ref "C127") (pin "2") (pinfunction "2_2") (pintype "passive"))
      (node (ref "C128") (pin "2") (pinfunction "2_2") (pintype "passive"))
      (node (ref "C129") (pin "2") (pinfunction "2_2") (pintype "passive"))
      (node (ref "C131") (pin "2") (pinfunction "2_2") (pintype "passive"))
      (node (ref "C133") (pin "2") (pinfunction "2_2") (pintype "passive"))
      (node (ref "C134") (pin "2") (pinfunction "2_2") (pintype "passive"))
      (node (ref "C135") (pin "2") (pinfunction "2_2") (pintype "passive"))
      (node (ref "C137") (pin "2") (pinfunction "2_2") (pintype "passive"))
      (node (ref "JP1") (pin "1") (pinfunction "COMMON_1") (pintype "passive"))
      (node (ref "L2") (pin "1") (pinfunction "1_1") (pintype "passive"))
      (node (ref "L5") (pin "1") (pinfunction "1_1") (pintype "passive"))
      (node (ref "SB1") (pin "1") (pinfunction "1_1") (pintype "passive"))
      (node (ref "SB11") (pin "1") (pinfunction "1_1") (pintype "passive"))
      (node (ref "U6") (pin "D11") (pinfunction "VDD_D11") (pintype "passive"))
      (node (ref "U6") (pin "D5") (pinfunction "VDD_D5") (pintype "passive"))
      (node (ref "U6") (pin "E12") (pinfunction "VDD_E12") (pintype "passive"))
      (node (ref "U6") (pin "E4") (pinfunction "VDD_E4") (pintype "passive"))
      (node (ref "U6") (pin "G4") (pinfunction "VDD_G4") (pintype "passive"))
      (node (ref "U6") (pin "H12") (pinfunction "VDD_H12") (pintype "passive"))
      (node (ref "U6") (pin "K4") (pinfunction "VDD_K4") (pintype "passive"))
      (node (ref "U6") (pin "L12") (pinfunction "VDD_L12") (pintype "passive"))
      (node (ref "U6") (pin "M5") (pinfunction "VDD_M5") (pintype "passive"))
      (node (ref "U6") (pin "M9") (pinfunction "VDD_M9") (pintype "passive"))
    )
    (net (code "21") (name "VDD_SDC") (class "Default")
      (node (ref "C23") (pin "1") (pinfunction "1_1") (pintype "passive"))
      (node (ref "C47") (pin "1") (pinfunction "1_1") (pintype "passive"))
      (node (ref "C54") (pin "1") (pinfunction "1_1") (pintype "passive"))
      (node (ref "L3") (pin "1") (pinfunction "1_1") (pintype "passive"))
      (node (ref "SB13") (pin "2") (pinfunction "2_2") (pintype "passive"))
      (node (ref "SB18") (pin "1") (pinfunction "1_1") (pintype "passive"))
      (node (ref "SB2") (pin "1") (pinfunction "1_1") (pintype "passive"))
      (node (ref "SB20") (pin "1") (pinfunction "1_1") (pintype "passive"))
      (node (ref "SB21") (pin "1") (pinfunction "1_1") (pintype "passive"))
      (node (ref "U6") (pin "G2") (pinfunction "VFBSD_G2") (pintype "passive"))
    )
    (net (code "22") (name "VIN") (class "Default")
      (node (ref "C97") (pin "2") (pinfunction "2_2") (pintype "passive"))
      (node (ref "U15") (pin "3") (pinfunction "Vin_3") (pintype "passive"))
    )
    (net (code "23") (name "VREF+") (class "Default")
      (node (ref "C120") (pin "2") (pinfunction "2_2") (pintype "passive"))
      (node (ref "C121") (pin "2") (pinfunction "2_2") (pintype "passive"))
      (node (ref "C26") (pin "2") (pinfunction "2_2") (pintype "passive"))
      (node (ref "R139") (pin "1") (pinfunction "1_1") (pintype "passive"))
      (node (ref "U1") (pin "5") (pinfunction "OUT_S_5") (pintype "passive"))
      (node (ref "U1") (pin "6") (pinfunction "OUT_F_6") (pintype "passive"))
      (node (ref "U6") (pin "M3") (pinfunction "VREFP_M3") (pintype "passive"))
    )
    (net (code "24") (name "unconnected-(U17-NC-Pad1)") (class "Default")
      (node (ref "U17") (pin "1") (pinfunction "NC_1") (pintype "passive+no_connect"))
    )
    (net (code "25") (name "unconnected-(U17-NC-Pad4)") (class "Default")
      (node (ref "U17") (pin "4") (pinfunction "NC_4") (pintype "passive+no_connect"))
    )
    (net (code "26") (name "unconnected-(U17-NC-Pad5)") (class "Default")
      (node (ref "U17") (pin "5") (pinfunction "NC_5") (pintype "passive+no_connect"))
    )
  )
)
